# LD1-001.net
KiCad netlist of a schematic drawn in EAGLE
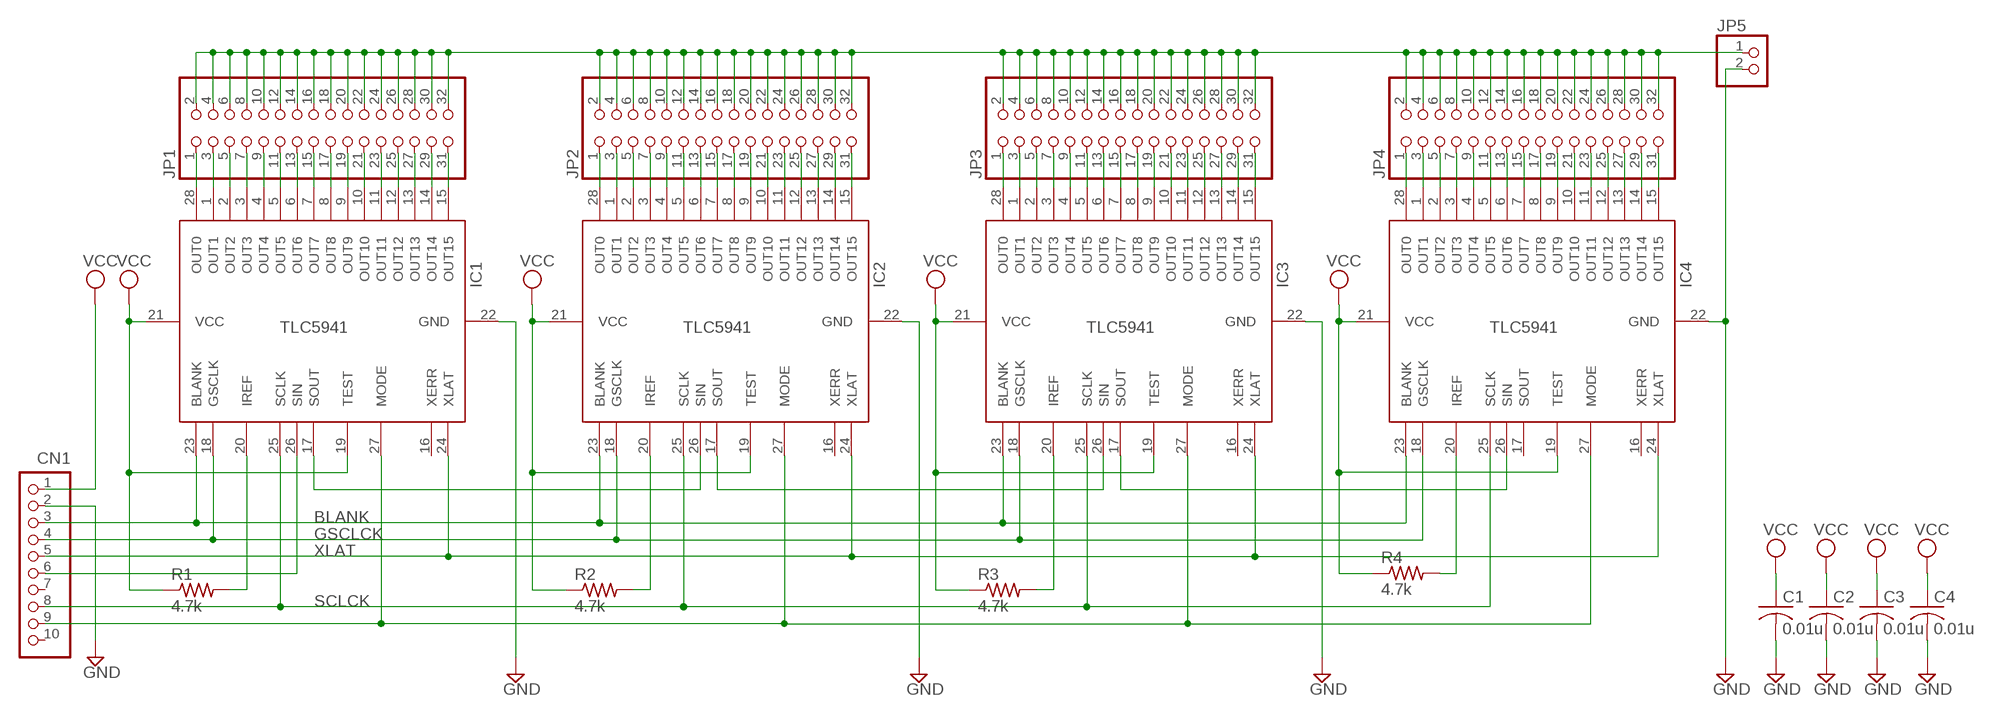
[diagram p0: schematic, sheet 1]

(export (version "E")
  (design (tool "Eeschema 10.0.6"))
  (components
    (comp (ref "C1")
      (value "0.01u")
      (footprint "eagle-import:C025-025X050")
      (libsource (lib "eagle-import") (part "C-US025-025X050"))
    )
    (comp (ref "C2")
      (value "0.01u")
      (footprint "eagle-import:C025-025X050")
      (libsource (lib "eagle-import") (part "C-US025-025X050"))
    )
    (comp (ref "C3")
      (value "0.01u")
      (footprint "eagle-import:C025-025X050")
      (libsource (lib "eagle-import") (part "C-US025-025X050"))
    )
    (comp (ref "C4")
      (value "0.01u")
      (footprint "eagle-import:C025-025X050")
      (libsource (lib "eagle-import") (part "C-US025-025X050"))
    )
    (comp (ref "CN1")
      (value "S10B-PH-K-S")
      (footprint "eagle-import:S10B-PH-K-S")
      (libsource (lib "eagle-import") (part "S10B-PH-K-S"))
    )
    (comp (ref "IC1")
      (value "TLC5941NT")
      (footprint "eagle-import:DIL28-3")
      (libsource (lib "eagle-import") (part "TLC5941NT"))
    )
    (comp (ref "IC2")
      (value "TLC5941NT")
      (footprint "eagle-import:DIL28-3")
      (libsource (lib "eagle-import") (part "TLC5941NT"))
    )
    (comp (ref "IC3")
      (value "TLC5941NT")
      (footprint "eagle-import:DIL28-3")
      (libsource (lib "eagle-import") (part "TLC5941NT"))
    )
    (comp (ref "IC4")
      (value "TLC5941NT")
      (footprint "eagle-import:DIL28-3")
      (libsource (lib "eagle-import") (part "TLC5941NT"))
    )
    (comp (ref "JP1")
      (value "PINHD-2X16")
      (footprint "eagle-import:2X16")
      (libsource (lib "eagle-import") (part "PINHD-2X16"))
    )
    (comp (ref "JP2")
      (value "PINHD-2X16")
      (footprint "eagle-import:2X16")
      (libsource (lib "eagle-import") (part "PINHD-2X16"))
    )
    (comp (ref "JP3")
      (value "PINHD-2X16")
      (footprint "eagle-import:2X16")
      (libsource (lib "eagle-import") (part "PINHD-2X16"))
    )
    (comp (ref "JP4")
      (value "PINHD-2X16")
      (footprint "eagle-import:2X16")
      (libsource (lib "eagle-import") (part "PINHD-2X16"))
    )
    (comp (ref "JP5")
      (value "PINHD-1X2")
      (footprint "eagle-import:1X02")
      (libsource (lib "eagle-import") (part "PINHD-1X2"))
    )
    (comp (ref "R1")
      (value "4.7k")
      (footprint "eagle-import:0204_5")
      (libsource (lib "eagle-import") (part "R-US_0204/5"))
    )
    (comp (ref "R2")
      (value "4.7k")
      (footprint "eagle-import:0204_5")
      (libsource (lib "eagle-import") (part "R-US_0204/5"))
    )
    (comp (ref "R3")
      (value "4.7k")
      (footprint "eagle-import:0204_5")
      (libsource (lib "eagle-import") (part "R-US_0204/5"))
    )
    (comp (ref "R4")
      (value "4.7k")
      (footprint "eagle-import:0204_5")
      (libsource (lib "eagle-import") (part "R-US_0204/5"))
    )
  )
  (nets
    (net (code "1") (name "/BLANK") (class "Default")
      (node (ref "CN1") (pin "3") (pinfunction "3_3") (pintype "passive"))
      (node (ref "IC1") (pin "23") (pinfunction "BLANK_23") (pintype "input"))
      (node (ref "IC2") (pin "23") (pinfunction "BLANK_23") (pintype "input"))
      (node (ref "IC3") (pin "23") (pinfunction "BLANK_23") (pintype "input"))
      (node (ref "IC4") (pin "23") (pinfunction "BLANK_23") (pintype "input"))
    )
    (net (code "2") (name "/GSCLCK") (class "Default")
      (node (ref "CN1") (pin "4") (pinfunction "4_4") (pintype "passive"))
      (node (ref "IC1") (pin "18") (pinfunction "GSCLK_18") (pintype "input"))
      (node (ref "IC2") (pin "18") (pinfunction "GSCLK_18") (pintype "input"))
      (node (ref "IC3") (pin "18") (pinfunction "GSCLK_18") (pintype "input"))
      (node (ref "IC4") (pin "18") (pinfunction "GSCLK_18") (pintype "input"))
    )
    (net (code "3") (name "/SCLCK") (class "Default")
      (node (ref "CN1") (pin "8") (pinfunction "8_8") (pintype "passive"))
      (node (ref "IC1") (pin "25") (pinfunction "SCLK_25") (pintype "input"))
      (node (ref "IC2") (pin "25") (pinfunction "SCLK_25") (pintype "input"))
      (node (ref "IC3") (pin "25") (pinfunction "SCLK_25") (pintype "input"))
      (node (ref "IC4") (pin "25") (pinfunction "SCLK_25") (pintype "input"))
    )
    (net (code "4") (name "/XLAT") (class "Default")
      (node (ref "CN1") (pin "5") (pinfunction "5_5") (pintype "passive"))
      (node (ref "IC1") (pin "24") (pinfunction "XLAT_24") (pintype "input"))
      (node (ref "IC2") (pin "24") (pinfunction "XLAT_24") (pintype "input"))
      (node (ref "IC3") (pin "24") (pinfunction "XLAT_24") (pintype "input"))
      (node (ref "IC4") (pin "24") (pinfunction "XLAT_24") (pintype "input"))
    )
    (net (code "5") (name "GND") (class "Default")
      (node (ref "C1") (pin "2") (pinfunction "2_2") (pintype "passive"))
      (node (ref "C2") (pin "2") (pinfunction "2_2") (pintype "passive"))
      (node (ref "C3") (pin "2") (pinfunction "2_2") (pintype "passive"))
      (node (ref "C4") (pin "2") (pinfunction "2_2") (pintype "passive"))
      (node (ref "CN1") (pin "2") (pinfunction "2_2") (pintype "passive"))
      (node (ref "IC1") (pin "22") (pinfunction "GND_22") (pintype "power_in"))
      (node (ref "IC2") (pin "22") (pinfunction "GND_22") (pintype "power_in"))
      (node (ref "IC3") (pin "22") (pinfunction "GND_22") (pintype "power_in"))
      (node (ref "IC4") (pin "22") (pinfunction "GND_22") (pintype "power_in"))
      (node (ref "JP5") (pin "2") (pinfunction "2_2") (pintype "passive"))
    )
    (net (code "6") (name "Net-(IC1-IREF)") (class "Default")
      (node (ref "IC1") (pin "20") (pinfunction "IREF_20") (pintype "bidirectional"))
      (node (ref "R1") (pin "2") (pinfunction "2_2") (pintype "passive"))
    )
    (net (code "7") (name "Net-(IC1-MODE)") (class "Default")
      (node (ref "CN1") (pin "9") (pinfunction "9_9") (pintype "passive"))
      (node (ref "IC1") (pin "27") (pinfunction "MODE_27") (pintype "input"))
      (node (ref "IC2") (pin "27") (pinfunction "MODE_27") (pintype "input"))
      (node (ref "IC3") (pin "27") (pinfunction "MODE_27") (pintype "input"))
      (node (ref "IC4") (pin "27") (pinfunction "MODE_27") (pintype "input"))
    )
    (net (code "8") (name "Net-(IC1-OUT0)") (class "Default")
      (node (ref "IC1") (pin "28") (pinfunction "OUT0_28") (pintype "output"))
      (node (ref "JP1") (pin "1") (pinfunction "1_1") (pintype "passive"))
    )
    (net (code "9") (name "Net-(IC1-OUT1)") (class "Default")
      (node (ref "IC1") (pin "1") (pinfunction "OUT1_1") (pintype "output"))
      (node (ref "JP1") (pin "3") (pinfunction "3_3") (pintype "passive"))
    )
    (net (code "10") (name "Net-(IC1-OUT2)") (class "Default")
      (node (ref "IC1") (pin "2") (pinfunction "OUT2_2") (pintype "output"))
      (node (ref "JP1") (pin "5") (pinfunction "5_5") (pintype "passive"))
    )
    (net (code "11") (name "Net-(IC1-OUT3)") (class "Default")
      (node (ref "IC1") (pin "3") (pinfunction "OUT3_3") (pintype "output"))
      (node (ref "JP1") (pin "7") (pinfunction "7_7") (pintype "passive"))
    )
    (net (code "12") (name "Net-(IC1-OUT4)") (class "Default")
      (node (ref "IC1") (pin "4") (pinfunction "OUT4_4") (pintype "output"))
      (node (ref "JP1") (pin "9") (pinfunction "9_9") (pintype "passive"))
    )
    (net (code "13") (name "Net-(IC1-OUT5)") (class "Default")
      (node (ref "IC1") (pin "5") (pinfunction "OUT5_5") (pintype "output"))
      (node (ref "JP1") (pin "11") (pinfunction "11_11") (pintype "passive"))
    )
    (net (code "14") (name "Net-(IC1-OUT6)") (class "Default")
      (node (ref "IC1") (pin "6") (pinfunction "OUT6_6") (pintype "output"))
      (node (ref "JP1") (pin "13") (pinfunction "13_13") (pintype "passive"))
    )
    (net (code "15") (name "Net-(IC1-OUT7)") (class "Default")
      (node (ref "IC1") (pin "7") (pinfunction "OUT7_7") (pintype "output"))
      (node (ref "JP1") (pin "15") (pinfunction "15_15") (pintype "passive"))
    )
    (net (code "16") (name "Net-(IC1-OUT8)") (class "Default")
      (node (ref "IC1") (pin "8") (pinfunction "OUT8_8") (pintype "output"))
      (node (ref "JP1") (pin "17") (pinfunction "17_17") (pintype "passive"))
    )
    (net (code "17") (name "Net-(IC1-OUT9)") (class "Default")
      (node (ref "IC1") (pin "9") (pinfunction "OUT9_9") (pintype "output"))
      (node (ref "JP1") (pin "19") (pinfunction "19_19") (pintype "passive"))
    )
    (net (code "18") (name "Net-(IC1-OUT10)") (class "Default")
      (node (ref "IC1") (pin "10") (pinfunction "OUT10_10") (pintype "output"))
      (node (ref "JP1") (pin "21") (pinfunction "21_21") (pintype "passive"))
    )
    (net (code "19") (name "Net-(IC1-OUT11)") (class "Default")
      (node (ref "IC1") (pin "11") (pinfunction "OUT11_11") (pintype "output"))
      (node (ref "JP1") (pin "23") (pinfunction "23_23") (pintype "passive"))
    )
    (net (code "20") (name "Net-(IC1-OUT12)") (class "Default")
      (node (ref "IC1") (pin "12") (pinfunction "OUT12_12") (pintype "output"))
      (node (ref "JP1") (pin "25") (pinfunction "25_25") (pintype "passive"))
    )
    (net (code "21") (name "Net-(IC1-OUT13)") (class "Default")
      (node (ref "IC1") (pin "13") (pinfunction "OUT13_13") (pintype "output"))
      (node (ref "JP1") (pin "27") (pinfunction "27_27") (pintype "passive"))
    )
    (net (code "22") (name "Net-(IC1-OUT14)") (class "Default")
      (node (ref "IC1") (pin "14") (pinfunction "OUT14_14") (pintype "output"))
      (node (ref "JP1") (pin "29") (pinfunction "29_29") (pintype "passive"))
    )
    (net (code "23") (name "Net-(IC1-OUT15)") (class "Default")
      (node (ref "IC1") (pin "15") (pinfunction "OUT15_15") (pintype "output"))
      (node (ref "JP1") (pin "31") (pinfunction "31_31") (pintype "passive"))
    )
    (net (code "24") (name "Net-(IC1-SIN)") (class "Default")
      (node (ref "CN1") (pin "6") (pinfunction "6_6") (pintype "passive"))
      (node (ref "IC1") (pin "26") (pinfunction "SIN_26") (pintype "input"))
    )
    (net (code "25") (name "Net-(IC1-SOUT)") (class "Default")
      (node (ref "IC1") (pin "17") (pinfunction "SOUT_17") (pintype "output"))
      (node (ref "IC2") (pin "26") (pinfunction "SIN_26") (pintype "input"))
    )
    (net (code "26") (name "Net-(IC2-IREF)") (class "Default")
      (node (ref "IC2") (pin "20") (pinfunction "IREF_20") (pintype "bidirectional"))
      (node (ref "R2") (pin "2") (pinfunction "2_2") (pintype "passive"))
    )
    (net (code "27") (name "Net-(IC2-OUT0)") (class "Default")
      (node (ref "IC2") (pin "28") (pinfunction "OUT0_28") (pintype "output"))
      (node (ref "JP2") (pin "1") (pinfunction "1_1") (pintype "passive"))
    )
    (net (code "28") (name "Net-(IC2-OUT1)") (class "Default")
      (node (ref "IC2") (pin "1") (pinfunction "OUT1_1") (pintype "output"))
      (node (ref "JP2") (pin "3") (pinfunction "3_3") (pintype "passive"))
    )
    (net (code "29") (name "Net-(IC2-OUT2)") (class "Default")
      (node (ref "IC2") (pin "2") (pinfunction "OUT2_2") (pintype "output"))
      (node (ref "JP2") (pin "5") (pinfunction "5_5") (pintype "passive"))
    )
    (net (code "30") (name "Net-(IC2-OUT3)") (class "Default")
      (node (ref "IC2") (pin "3") (pinfunction "OUT3_3") (pintype "output"))
      (node (ref "JP2") (pin "7") (pinfunction "7_7") (pintype "passive"))
    )
    (net (code "31") (name "Net-(IC2-OUT4)") (class "Default")
      (node (ref "IC2") (pin "4") (pinfunction "OUT4_4") (pintype "output"))
      (node (ref "JP2") (pin "9") (pinfunction "9_9") (pintype "passive"))
    )
    (net (code "32") (name "Net-(IC2-OUT5)") (class "Default")
      (node (ref "IC2") (pin "5") (pinfunction "OUT5_5") (pintype "output"))
      (node (ref "JP2") (pin "11") (pinfunction "11_11") (pintype "passive"))
    )
    (net (code "33") (name "Net-(IC2-OUT6)") (class "Default")
      (node (ref "IC2") (pin "6") (pinfunction "OUT6_6") (pintype "output"))
      (node (ref "JP2") (pin "13") (pinfunction "13_13") (pintype "passive"))
    )
    (net (code "34") (name "Net-(IC2-OUT7)") (class "Default")
      (node (ref "IC2") (pin "7") (pinfunction "OUT7_7") (pintype "output"))
      (node (ref "JP2") (pin "15") (pinfunction "15_15") (pintype "passive"))
    )
    (net (code "35") (name "Net-(IC2-OUT8)") (class "Default")
      (node (ref "IC2") (pin "8") (pinfunction "OUT8_8") (pintype "output"))
      (node (ref "JP2") (pin "17") (pinfunction "17_17") (pintype "passive"))
    )
    (net (code "36") (name "Net-(IC2-OUT9)") (class "Default")
      (node (ref "IC2") (pin "9") (pinfunction "OUT9_9") (pintype "output"))
      (node (ref "JP2") (pin "19") (pinfunction "19_19") (pintype "passive"))
    )
    (net (code "37") (name "Net-(IC2-OUT10)") (class "Default")
      (node (ref "IC2") (pin "10") (pinfunction "OUT10_10") (pintype "output"))
      (node (ref "JP2") (pin "21") (pinfunction "21_21") (pintype "passive"))
    )
    (net (code "38") (name "Net-(IC2-OUT11)") (class "Default")
      (node (ref "IC2") (pin "11") (pinfunction "OUT11_11") (pintype "output"))
      (node (ref "JP2") (pin "23") (pinfunction "23_23") (pintype "passive"))
    )
    (net (code "39") (name "Net-(IC2-OUT12)") (class "Default")
      (node (ref "IC2") (pin "12") (pinfunction "OUT12_12") (pintype "output"))
      (node (ref "JP2") (pin "25") (pinfunction "25_25") (pintype "passive"))
    )
    (net (code "40") (name "Net-(IC2-OUT13)") (class "Default")
      (node (ref "IC2") (pin "13") (pinfunction "OUT13_13") (pintype "output"))
      (node (ref "JP2") (pin "27") (pinfunction "27_27") (pintype "passive"))
    )
    (net (code "41") (name "Net-(IC2-OUT14)") (class "Default")
      (node (ref "IC2") (pin "14") (pinfunction "OUT14_14") (pintype "output"))
      (node (ref "JP2") (pin "29") (pinfunction "29_29") (pintype "passive"))
    )
    (net (code "42") (name "Net-(IC2-OUT15)") (class "Default")
      (node (ref "IC2") (pin "15") (pinfunction "OUT15_15") (pintype "output"))
      (node (ref "JP2") (pin "31") (pinfunction "31_31") (pintype "passive"))
    )
    (net (code "43") (name "Net-(IC2-SOUT)") (class "Default")
      (node (ref "IC2") (pin "17") (pinfunction "SOUT_17") (pintype "output"))
      (node (ref "IC3") (pin "26") (pinfunction "SIN_26") (pintype "input"))
    )
    (net (code "44") (name "Net-(IC3-IREF)") (class "Default")
      (node (ref "IC3") (pin "20") (pinfunction "IREF_20") (pintype "bidirectional"))
      (node (ref "R3") (pin "2") (pinfunction "2_2") (pintype "passive"))
    )
    (net (code "45") (name "Net-(IC3-OUT0)") (class "Default")
      (node (ref "IC3") (pin "28") (pinfunction "OUT0_28") (pintype "output"))
      (node (ref "JP3") (pin "1") (pinfunction "1_1") (pintype "passive"))
    )
    (net (code "46") (name "Net-(IC3-OUT1)") (class "Default")
      (node (ref "IC3") (pin "1") (pinfunction "OUT1_1") (pintype "output"))
      (node (ref "JP3") (pin "3") (pinfunction "3_3") (pintype "passive"))
    )
    (net (code "47") (name "Net-(IC3-OUT2)") (class "Default")
      (node (ref "IC3") (pin "2") (pinfunction "OUT2_2") (pintype "output"))
      (node (ref "JP3") (pin "5") (pinfunction "5_5") (pintype "passive"))
    )
    (net (code "48") (name "Net-(IC3-OUT3)") (class "Default")
      (node (ref "IC3") (pin "3") (pinfunction "OUT3_3") (pintype "output"))
      (node (ref "JP3") (pin "7") (pinfunction "7_7") (pintype "passive"))
    )
    (net (code "49") (name "Net-(IC3-OUT4)") (class "Default")
      (node (ref "IC3") (pin "4") (pinfunction "OUT4_4") (pintype "output"))
      (node (ref "JP3") (pin "9") (pinfunction "9_9") (pintype "passive"))
    )
    (net (code "50") (name "Net-(IC3-OUT5)") (class "Default")
      (node (ref "IC3") (pin "5") (pinfunction "OUT5_5") (pintype "output"))
      (node (ref "JP3") (pin "11") (pinfunction "11_11") (pintype "passive"))
    )
    (net (code "51") (name "Net-(IC3-OUT6)") (class "Default")
      (node (ref "IC3") (pin "6") (pinfunction "OUT6_6") (pintype "output"))
      (node (ref "JP3") (pin "13") (pinfunction "13_13") (pintype "passive"))
    )
    (net (code "52") (name "Net-(IC3-OUT7)") (class "Default")
      (node (ref "IC3") (pin "7") (pinfunction "OUT7_7") (pintype "output"))
      (node (ref "JP3") (pin "15") (pinfunction "15_15") (pintype "passive"))
    )
    (net (code "53") (name "Net-(IC3-OUT8)") (class "Default")
      (node (ref "IC3") (pin "8") (pinfunction "OUT8_8") (pintype "output"))
      (node (ref "JP3") (pin "17") (pinfunction "17_17") (pintype "passive"))
    )
    (net (code "54") (name "Net-(IC3-OUT9)") (class "Default")
      (node (ref "IC3") (pin "9") (pinfunction "OUT9_9") (pintype "output"))
      (node (ref "JP3") (pin "19") (pinfunction "19_19") (pintype "passive"))
    )
    (net (code "55") (name "Net-(IC3-OUT10)") (class "Default")
      (node (ref "IC3") (pin "10") (pinfunction "OUT10_10") (pintype "output"))
      (node (ref "JP3") (pin "21") (pinfunction "21_21") (pintype "passive"))
    )
    (net (code "56") (name "Net-(IC3-OUT11)") (class "Default")
      (node (ref "IC3") (pin "11") (pinfunction "OUT11_11") (pintype "output"))
      (node (ref "JP3") (pin "23") (pinfunction "23_23") (pintype "passive"))
    )
    (net (code "57") (name "Net-(IC3-OUT12)") (class "Default")
      (node (ref "IC3") (pin "12") (pinfunction "OUT12_12") (pintype "output"))
      (node (ref "JP3") (pin "25") (pinfunction "25_25") (pintype "passive"))
    )
    (net (code "58") (name "Net-(IC3-OUT13)") (class "Default")
      (node (ref "IC3") (pin "13") (pinfunction "OUT13_13") (pintype "output"))
      (node (ref "JP3") (pin "27") (pinfunction "27_27") (pintype "passive"))
    )
    (net (code "59") (name "Net-(IC3-OUT14)") (class "Default")
      (node (ref "IC3") (pin "14") (pinfunction "OUT14_14") (pintype "output"))
      (node (ref "JP3") (pin "29") (pinfunction "29_29") (pintype "passive"))
    )
    (net (code "60") (name "Net-(IC3-OUT15)") (class "Default")
      (node (ref "IC3") (pin "15") (pinfunction "OUT15_15") (pintype "output"))
      (node (ref "JP3") (pin "31") (pinfunction "31_31") (pintype "passive"))
    )
    (net (code "61") (name "Net-(IC3-SOUT)") (class "Default")
      (node (ref "IC3") (pin "17") (pinfunction "SOUT_17") (pintype "output"))
      (node (ref "IC4") (pin "26") (pinfunction "SIN_26") (pintype "input"))
    )
    (net (code "62") (name "Net-(IC4-IREF)") (class "Default")
      (node (ref "IC4") (pin "20") (pinfunction "IREF_20") (pintype "bidirectional"))
      (node (ref "R4") (pin "2") (pinfunction "2_2") (pintype "passive"))
    )
    (net (code "63") (name "Net-(IC4-OUT0)") (class "Default")
      (node (ref "IC4") (pin "28") (pinfunction "OUT0_28") (pintype "output"))
      (node (ref "JP4") (pin "1") (pinfunction "1_1") (pintype "passive"))
    )
    (net (code "64") (name "Net-(IC4-OUT1)") (class "Default")
      (node (ref "IC4") (pin "1") (pinfunction "OUT1_1") (pintype "output"))
      (node (ref "JP4") (pin "3") (pinfunction "3_3") (pintype "passive"))
    )
    (net (code "65") (name "Net-(IC4-OUT2)") (class "Default")
      (node (ref "IC4") (pin "2") (pinfunction "OUT2_2") (pintype "output"))
      (node (ref "JP4") (pin "5") (pinfunction "5_5") (pintype "passive"))
    )
    (net (code "66") (name "Net-(IC4-OUT3)") (class "Default")
      (node (ref "IC4") (pin "3") (pinfunction "OUT3_3") (pintype "output"))
      (node (ref "JP4") (pin "7") (pinfunction "7_7") (pintype "passive"))
    )
    (net (code "67") (name "Net-(IC4-OUT4)") (class "Default")
      (node (ref "IC4") (pin "4") (pinfunction "OUT4_4") (pintype "output"))
      (node (ref "JP4") (pin "9") (pinfunction "9_9") (pintype "passive"))
    )
    (net (code "68") (name "Net-(IC4-OUT5)") (class "Default")
      (node (ref "IC4") (pin "5") (pinfunction "OUT5_5") (pintype "output"))
      (node (ref "JP4") (pin "11") (pinfunction "11_11") (pintype "passive"))
    )
    (net (code "69") (name "Net-(IC4-OUT6)") (class "Default")
      (node (ref "IC4") (pin "6") (pinfunction "OUT6_6") (pintype "output"))
      (node (ref "JP4") (pin "13") (pinfunction "13_13") (pintype "passive"))
    )
    (net (code "70") (name "Net-(IC4-OUT7)") (class "Default")
      (node (ref "IC4") (pin "7") (pinfunction "OUT7_7") (pintype "output"))
      (node (ref "JP4") (pin "15") (pinfunction "15_15") (pintype "passive"))
    )
    (net (code "71") (name "Net-(IC4-OUT8)") (class "Default")
      (node (ref "IC4") (pin "8") (pinfunction "OUT8_8") (pintype "output"))
      (node (ref "JP4") (pin "17") (pinfunction "17_17") (pintype "passive"))
    )
    (net (code "72") (name "Net-(IC4-OUT9)") (class "Default")
      (node (ref "IC4") (pin "9") (pinfunction "OUT9_9") (pintype "output"))
      (node (ref "JP4") (pin "19") (pinfunction "19_19") (pintype "passive"))
    )
    (net (code "73") (name "Net-(IC4-OUT10)") (class "Default")
      (node (ref "IC4") (pin "10") (pinfunction "OUT10_10") (pintype "output"))
      (node (ref "JP4") (pin "21") (pinfunction "21_21") (pintype "passive"))
    )
    (net (code "74") (name "Net-(IC4-OUT11)") (class "Default")
      (node (ref "IC4") (pin "11") (pinfunction "OUT11_11") (pintype "output"))
      (node (ref "JP4") (pin "23") (pinfunction "23_23") (pintype "passive"))
    )
    (net (code "75") (name "Net-(IC4-OUT12)") (class "Default")
      (node (ref "IC4") (pin "12") (pinfunction "OUT12_12") (pintype "output"))
      (node (ref "JP4") (pin "25") (pinfunction "25_25") (pintype "passive"))
    )
    (net (code "76") (name "Net-(IC4-OUT13)") (class "Default")
      (node (ref "IC4") (pin "13") (pinfunction "OUT13_13") (pintype "output"))
      (node (ref "JP4") (pin "27") (pinfunction "27_27") (pintype "passive"))
    )
    (net (code "77") (name "Net-(IC4-OUT14)") (class "Default")
      (node (ref "IC4") (pin "14") (pinfunction "OUT14_14") (pintype "output"))
      (node (ref "JP4") (pin "29") (pinfunction "29_29") (pintype "passive"))
    )
    (net (code "78") (name "Net-(IC4-OUT15)") (class "Default")
      (node (ref "IC4") (pin "15") (pinfunction "OUT15_15") (pintype "output"))
      (node (ref "JP4") (pin "31") (pinfunction "31_31") (pintype "passive"))
    )
    (net (code "79") (name "Net-(JP1-Pad10)") (class "Default")
      (node (ref "JP1") (pin "10") (pinfunction "10_10") (pintype "passive"))
      (node (ref "JP1") (pin "12") (pinfunction "12_12") (pintype "passive"))
      (node (ref "JP1") (pin "14") (pinfunction "14_14") (pintype "passive"))
      (node (ref "JP1") (pin "16") (pinfunction "16_16") (pintype "passive"))
      (node (ref "JP1") (pin "18") (pinfunction "18_18") (pintype "passive"))
      (node (ref "JP1") (pin "2") (pinfunction "2_2") (pintype "passive"))
      (node (ref "JP1") (pin "20") (pinfunction "20_20") (pintype "passive"))
      (node (ref "JP1") (pin "22") (pinfunction "22_22") (pintype "passive"))
      (node (ref "JP1") (pin "24") (pinfunction "24_24") (pintype "passive"))
      (node (ref "JP1") (pin "26") (pinfunction "26_26") (pintype "passive"))
      (node (ref "JP1") (pin "28") (pinfunction "28_28") (pintype "passive"))
      (node (ref "JP1") (pin "30") (pinfunction "30_30") (pintype "passive"))
      (node (ref "JP1") (pin "32") (pinfunction "32_32") (pintype "passive"))
      (node (ref "JP1") (pin "4") (pinfunction "4_4") (pintype "passive"))
      (node (ref "JP1") (pin "6") (pinfunction "6_6") (pintype "passive"))
      (node (ref "JP1") (pin "8") (pinfunction "8_8") (pintype "passive"))
      (node (ref "JP2") (pin "10") (pinfunction "10_10") (pintype "passive"))
      (node (ref "JP2") (pin "12") (pinfunction "12_12") (pintype "passive"))
      (node (ref "JP2") (pin "14") (pinfunction "14_14") (pintype "passive"))
      (node (ref "JP2") (pin "16") (pinfunction "16_16") (pintype "passive"))
      (node (ref "JP2") (pin "18") (pinfunction "18_18") (pintype "passive"))
      (node (ref "JP2") (pin "2") (pinfunction "2_2") (pintype "passive"))
      (node (ref "JP2") (pin "20") (pinfunction "20_20") (pintype "passive"))
      (node (ref "JP2") (pin "22") (pinfunction "22_22") (pintype "passive"))
      (node (ref "JP2") (pin "24") (pinfunction "24_24") (pintype "passive"))
      (node (ref "JP2") (pin "26") (pinfunction "26_26") (pintype "passive"))
      (node (ref "JP2") (pin "28") (pinfunction "28_28") (pintype "passive"))
      (node (ref "JP2") (pin "30") (pinfunction "30_30") (pintype "passive"))
      (node (ref "JP2") (pin "32") (pinfunction "32_32") (pintype "passive"))
      (node (ref "JP2") (pin "4") (pinfunction "4_4") (pintype "passive"))
      (node (ref "JP2") (pin "6") (pinfunction "6_6") (pintype "passive"))
      (node (ref "JP2") (pin "8") (pinfunction "8_8") (pintype "passive"))
      (node (ref "JP3") (pin "10") (pinfunction "10_10") (pintype "passive"))
      (node (ref "JP3") (pin "12") (pinfunction "12_12") (pintype "passive"))
      (node (ref "JP3") (pin "14") (pinfunction "14_14") (pintype "passive"))
      (node (ref "JP3") (pin "16") (pinfunction "16_16") (pintype "passive"))
      (node (ref "JP3") (pin "18") (pinfunction "18_18") (pintype "passive"))
      (node (ref "JP3") (pin "2") (pinfunction "2_2") (pintype "passive"))
      (node (ref "JP3") (pin "20") (pinfunction "20_20") (pintype "passive"))
      (node (ref "JP3") (pin "22") (pinfunction "22_22") (pintype "passive"))
      (node (ref "JP3") (pin "24") (pinfunction "24_24") (pintype "passive"))
      (node (ref "JP3") (pin "26") (pinfunction "26_26") (pintype "passive"))
      (node (ref "JP3") (pin "28") (pinfunction "28_28") (pintype "passive"))
      (node (ref "JP3") (pin "30") (pinfunction "30_30") (pintype "passive"))
      (node (ref "JP3") (pin "32") (pinfunction "32_32") (pintype "passive"))
      (node (ref "JP3") (pin "4") (pinfunction "4_4") (pintype "passive"))
      (node (ref "JP3") (pin "6") (pinfunction "6_6") (pintype "passive"))
      (node (ref "JP3") (pin "8") (pinfunction "8_8") (pintype "passive"))
      (node (ref "JP4") (pin "10") (pinfunction "10_10") (pintype "passive"))
      (node (ref "JP4") (pin "12") (pinfunction "12_12") (pintype "passive"))
      (node (ref "JP4") (pin "14") (pinfunction "14_14") (pintype "passive"))
      (node (ref "JP4") (pin "16") (pinfunction "16_16") (pintype "passive"))
      (node (ref "JP4") (pin "18") (pinfunction "18_18") (pintype "passive"))
      (node (ref "JP4") (pin "2") (pinfunction "2_2") (pintype "passive"))
      (node (ref "JP4") (pin "20") (pinfunction "20_20") (pintype "passive"))
      (node (ref "JP4") (pin "22") (pinfunction "22_22") (pintype "passive"))
      (node (ref "JP4") (pin "24") (pinfunction "24_24") (pintype "passive"))
      (node (ref "JP4") (pin "26") (pinfunction "26_26") (pintype "passive"))
      (node (ref "JP4") (pin "28") (pinfunction "28_28") (pintype "passive"))
      (node (ref "JP4") (pin "30") (pinfunction "30_30") (pintype "passive"))
      (node (ref "JP4") (pin "32") (pinfunction "32_32") (pintype "passive"))
      (node (ref "JP4") (pin "4") (pinfunction "4_4") (pintype "passive"))
      (node (ref "JP4") (pin "6") (pinfunction "6_6") (pintype "passive"))
      (node (ref "JP4") (pin "8") (pinfunction "8_8") (pintype "passive"))
      (node (ref "JP5") (pin "1") (pinfunction "1_1") (pintype "passive"))
    )
    (net (code "80") (name "VCC") (class "Default")
      (node (ref "C1") (pin "1") (pinfunction "1_1") (pintype "passive"))
      (node (ref "C2") (pin "1") (pinfunction "1_1") (pintype "passive"))
      (node (ref "C3") (pin "1") (pinfunction "1_1") (pintype "passive"))
      (node (ref "C4") (pin "1") (pinfunction "1_1") (pintype "passive"))
      (node (ref "CN1") (pin "1") (pinfunction "1_1") (pintype "passive"))
      (node (ref "IC1") (pin "19") (pinfunction "TEST_19") (pintype "input"))
      (node (ref "IC1") (pin "21") (pinfunction "VCC_21") (pintype "power_in"))
      (node (ref "IC2") (pin "19") (pinfunction "TEST_19") (pintype "input"))
      (node (ref "IC2") (pin "21") (pinfunction "VCC_21") (pintype "power_in"))
      (node (ref "IC3") (pin "19") (pinfunction "TEST_19") (pintype "input"))
      (node (ref "IC3") (pin "21") (pinfunction "VCC_21") (pintype "power_in"))
      (node (ref "IC4") (pin "19") (pinfunction "TEST_19") (pintype "input"))
      (node (ref "IC4") (pin "21") (pinfunction "VCC_21") (pintype "power_in"))
      (node (ref "R1") (pin "1") (pinfunction "1_1") (pintype "passive"))
      (node (ref "R2") (pin "1") (pinfunction "1_1") (pintype "passive"))
      (node (ref "R3") (pin "1") (pinfunction "1_1") (pintype "passive"))
      (node (ref "R4") (pin "1") (pinfunction "1_1") (pintype "passive"))
    )
    (net (code "81") (name "unconnected-(CN1-Pad7)") (class "Default")
      (node (ref "CN1") (pin "7") (pinfunction "7_7") (pintype "passive"))
    )
    (net (code "82") (name "unconnected-(CN1-Pad10)") (class "Default")
      (node (ref "CN1") (pin "10") (pinfunction "10_10") (pintype "passive"))
    )
    (net (code "83") (name "unconnected-(IC1-XERR-Pad16)") (class "Default")
      (node (ref "IC1") (pin "16") (pinfunction "XERR_16") (pintype "output"))
    )
    (net (code "84") (name "unconnected-(IC2-XERR-Pad16)") (class "Default")
      (node (ref "IC2") (pin "16") (pinfunction "XERR_16") (pintype "output"))
    )
    (net (code "85") (name "unconnected-(IC3-XERR-Pad16)") (class "Default")
      (node (ref "IC3") (pin "16") (pinfunction "XERR_16") (pintype "output"))
    )
    (net (code "86") (name "unconnected-(IC4-SOUT-Pad17)") (class "Default")
      (node (ref "IC4") (pin "17") (pinfunction "SOUT_17") (pintype "output"))
    )
    (net (code "87") (name "unconnected-(IC4-XERR-Pad16)") (class "Default")
      (node (ref "IC4") (pin "16") (pinfunction "XERR_16") (pintype "output"))
    )
  )
)
